# SCH_New-Project2_2024-12-12_1.net
KiCad netlist of a schematic drawn in EasyEDA
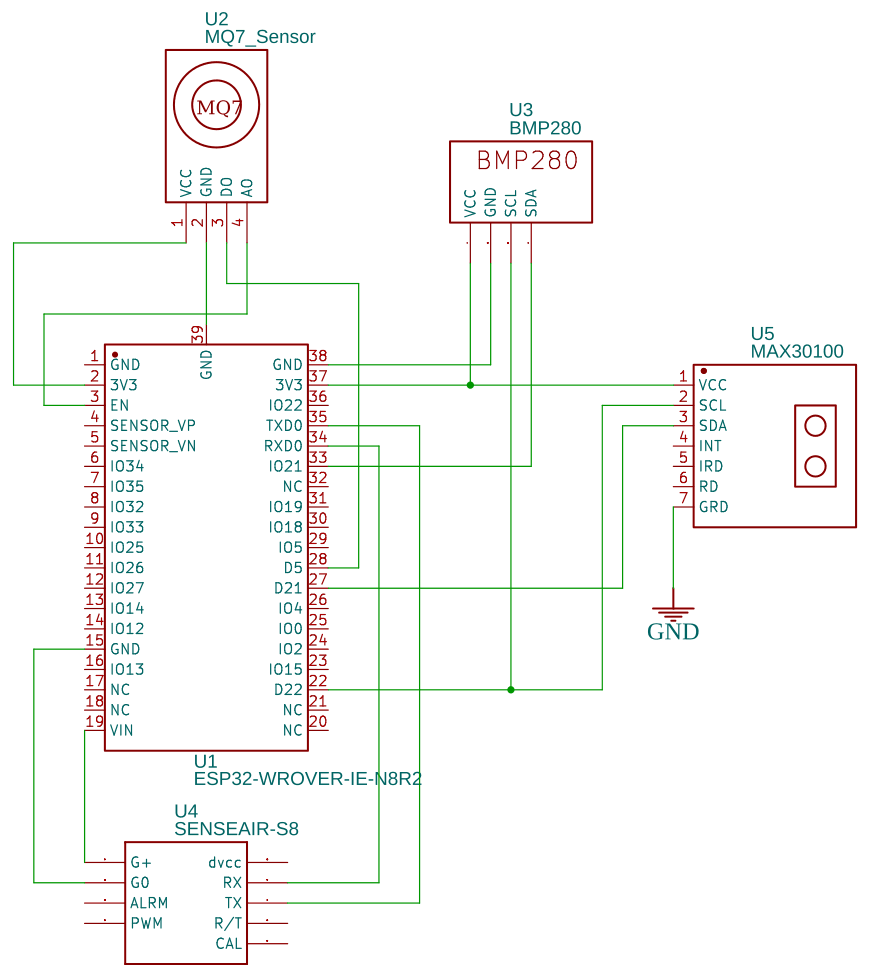
[diagram p0: schematic sheet]

(export (version "E")
  (design (tool "Eeschema 10.0.6"))
  (components
    (comp (ref "U1")
      (value "ESP32-WROVER-IE-N8R2")
      (fields (field (name "Manufacturer") "ESPRESSIF(乐鑫)"))
      (libsource (lib "") (part "ESP32-WROVER-IE-N8R2"))
    )
    (comp (ref "U2") (value "MQ7_Sensor") (libsource (lib "") (part "MQ7_Sensor")))
    (comp (ref "U3") (value "BMP280") (libsource (lib "") (part "BMP280")))
    (comp (ref "U4")
      (value "SENSEAIR-S8")
      (fields (field (name "Manufacturer Part") "SENSEAIR S8"))
      (libsource (lib "") (part "SENSEAIR-S8"))
    )
    (comp (ref "U5")
      (value "MAX30100")
      (fields (field (name "Manufacturer Part") "MAX30100EFD+") (field (name "Manufacturer") "MAXIM"))
      (libsource (lib "") (part "MAX30100"))
    )
  )
  (nets
    (net (code "1") (name "GND") (class "Default")
      (node (ref "U5") (pin "7") (pinfunction "GRD_7") (pintype "unspecified"))
    )
    (net (code "2") (name "Net-(U1-D5)") (class "Default")
      (node (ref "U1") (pin "28") (pinfunction "D5_28") (pintype "unspecified"))
      (node (ref "U2") (pin "3") (pinfunction "DO_3") (pintype "unspecified"))
    )
    (net (code "3") (name "Net-(U1-D21)") (class "Default")
      (node (ref "U1") (pin "27") (pinfunction "D21_27") (pintype "unspecified"))
      (node (ref "U5") (pin "3") (pinfunction "SDA_3") (pintype "unspecified"))
    )
    (net (code "4") (name "Net-(U1-D22)") (class "Default")
      (node (ref "U1") (pin "22") (pinfunction "D22_22") (pintype "unspecified"))
      (node (ref "U3") (pin "5") (pinfunction "SCL_5") (pintype "unspecified"))
      (node (ref "U5") (pin "2") (pinfunction "SCL_2") (pintype "unspecified"))
    )
    (net (code "5") (name "Net-(U1-EN)") (class "Default")
      (node (ref "U1") (pin "3") (pinfunction "EN_3") (pintype "unspecified"))
      (node (ref "U2") (pin "4") (pinfunction "AO_4") (pintype "unspecified"))
    )
    (net (code "6") (name "Net-(U1-GND-Pad15)") (class "Default")
      (node (ref "U1") (pin "15") (pinfunction "GND_15") (pintype "unspecified"))
      (node (ref "U4") (pin "G0") (pinfunction "G0_G0") (pintype "unspecified"))
    )
    (net (code "7") (name "Net-(U1-IO21)") (class "Default")
      (node (ref "U1") (pin "33") (pinfunction "IO21_33") (pintype "unspecified"))
      (node (ref "U3") (pin "4") (pinfunction "SDA_4") (pintype "unspecified"))
    )
    (net (code "8") (name "Net-(U1-RXD0)") (class "Default")
      (node (ref "U1") (pin "34") (pinfunction "RXD0_34") (pintype "unspecified"))
      (node (ref "U4") (pin "RX") (pinfunction "RX_RX") (pintype "unspecified"))
    )
    (net (code "9") (name "Net-(U1-TXD0)") (class "Default")
      (node (ref "U1") (pin "35") (pinfunction "TXD0_35") (pintype "unspecified"))
      (node (ref "U4") (pin "TX") (pinfunction "TX_TX") (pintype "unspecified"))
    )
    (net (code "10") (name "Net-(U1-VIN)") (class "Default")
      (node (ref "U1") (pin "19") (pinfunction "VIN_19") (pintype "unspecified"))
      (node (ref "U4") (pin "G+") (pinfunction "G+_G+") (pintype "unspecified"))
    )
    (net (code "11") (name "Net-(U2-GND)") (class "Default")
      (node (ref "U1") (pin "39") (pinfunction "GND_39") (pintype "unspecified"))
      (node (ref "U2") (pin "2") (pinfunction "GND_2") (pintype "unspecified"))
    )
    (net (code "12") (name "Net-(U2-VCC)") (class "Default")
      (node (ref "U1") (pin "2") (pinfunction "3V3_2") (pintype "unspecified"))
      (node (ref "U2") (pin "1") (pinfunction "VCC_1") (pintype "unspecified"))
    )
    (net (code "13") (name "Net-(U3-GND)") (class "Default")
      (node (ref "U1") (pin "38") (pinfunction "GND_38") (pintype "unspecified"))
      (node (ref "U3") (pin "6") (pinfunction "GND_6") (pintype "unspecified"))
    )
    (net (code "14") (name "Net-(U3-VCC)") (class "Default")
      (node (ref "U1") (pin "37") (pinfunction "3V3_37") (pintype "unspecified"))
      (node (ref "U3") (pin "7") (pinfunction "VCC_7") (pintype "unspecified"))
      (node (ref "U5") (pin "1") (pinfunction "VCC_1") (pintype "unspecified"))
    )
    (net (code "15") (name "unconnected-(U1-GND-Pad1)") (class "Default")
      (node (ref "U1") (pin "1") (pinfunction "GND_1") (pintype "unspecified"))
    )
    (net (code "16") (name "unconnected-(U1-IO0-Pad25)") (class "Default")
      (node (ref "U1") (pin "25") (pinfunction "IO0_25") (pintype "unspecified"))
    )
    (net (code "17") (name "unconnected-(U1-IO2-Pad24)") (class "Default")
      (node (ref "U1") (pin "24") (pinfunction "IO2_24") (pintype "unspecified"))
    )
    (net (code "18") (name "unconnected-(U1-IO4-Pad26)") (class "Default")
      (node (ref "U1") (pin "26") (pinfunction "IO4_26") (pintype "unspecified"))
    )
    (net (code "19") (name "unconnected-(U1-IO5-Pad29)") (class "Default")
      (node (ref "U1") (pin "29") (pinfunction "IO5_29") (pintype "unspecified"))
    )
    (net (code "20") (name "unconnected-(U1-IO12-Pad14)") (class "Default")
      (node (ref "U1") (pin "14") (pinfunction "IO12_14") (pintype "unspecified"))
    )
    (net (code "21") (name "unconnected-(U1-IO13-Pad16)") (class "Default")
      (node (ref "U1") (pin "16") (pinfunction "IO13_16") (pintype "unspecified"))
    )
    (net (code "22") (name "unconnected-(U1-IO14-Pad13)") (class "Default")
      (node (ref "U1") (pin "13") (pinfunction "IO14_13") (pintype "unspecified"))
    )
    (net (code "23") (name "unconnected-(U1-IO15-Pad23)") (class "Default")
      (node (ref "U1") (pin "23") (pinfunction "IO15_23") (pintype "unspecified"))
    )
    (net (code "24") (name "unconnected-(U1-IO18-Pad30)") (class "Default")
      (node (ref "U1") (pin "30") (pinfunction "IO18_30") (pintype "unspecified"))
    )
    (net (code "25") (name "unconnected-(U1-IO19-Pad31)") (class "Default")
      (node (ref "U1") (pin "31") (pinfunction "IO19_31") (pintype "unspecified"))
    )
    (net (code "26") (name "unconnected-(U1-IO22-Pad36)") (class "Default")
      (node (ref "U1") (pin "36") (pinfunction "IO22_36") (pintype "unspecified"))
    )
    (net (code "27") (name "unconnected-(U1-IO25-Pad10)") (class "Default")
      (node (ref "U1") (pin "10") (pinfunction "IO25_10") (pintype "unspecified"))
    )
    (net (code "28") (name "unconnected-(U1-IO26-Pad11)") (class "Default")
      (node (ref "U1") (pin "11") (pinfunction "IO26_11") (pintype "unspecified"))
    )
    (net (code "29") (name "unconnected-(U1-IO27-Pad12)") (class "Default")
      (node (ref "U1") (pin "12") (pinfunction "IO27_12") (pintype "unspecified"))
    )
    (net (code "30") (name "unconnected-(U1-IO32-Pad8)") (class "Default")
      (node (ref "U1") (pin "8") (pinfunction "IO32_8") (pintype "unspecified"))
    )
    (net (code "31") (name "unconnected-(U1-IO33-Pad9)") (class "Default")
      (node (ref "U1") (pin "9") (pinfunction "IO33_9") (pintype "unspecified"))
    )
    (net (code "32") (name "unconnected-(U1-IO34-Pad6)") (class "Default")
      (node (ref "U1") (pin "6") (pinfunction "IO34_6") (pintype "unspecified"))
    )
    (net (code "33") (name "unconnected-(U1-IO35-Pad7)") (class "Default")
      (node (ref "U1") (pin "7") (pinfunction "IO35_7") (pintype "unspecified"))
    )
    (net (code "34") (name "unconnected-(U1-NC-Pad17)") (class "Default")
      (node (ref "U1") (pin "17") (pinfunction "NC_17") (pintype "unspecified"))
    )
    (net (code "35") (name "unconnected-(U1-NC-Pad18)") (class "Default")
      (node (ref "U1") (pin "18") (pinfunction "NC_18") (pintype "unspecified"))
    )
    (net (code "36") (name "unconnected-(U1-NC-Pad20)") (class "Default")
      (node (ref "U1") (pin "20") (pinfunction "NC_20") (pintype "unspecified"))
    )
    (net (code "37") (name "unconnected-(U1-NC-Pad21)") (class "Default")
      (node (ref "U1") (pin "21") (pinfunction "NC_21") (pintype "unspecified"))
    )
    (net (code "38") (name "unconnected-(U1-NC-Pad32)") (class "Default")
      (node (ref "U1") (pin "32") (pinfunction "NC_32") (pintype "unspecified"))
    )
    (net (code "39") (name "unconnected-(U1-SENSOR_VN-Pad5)") (class "Default")
      (node (ref "U1") (pin "5") (pinfunction "SENSOR_VN_5") (pintype "unspecified"))
    )
    (net (code "40") (name "unconnected-(U1-SENSOR_VP-Pad4)") (class "Default")
      (node (ref "U1") (pin "4") (pinfunction "SENSOR_VP_4") (pintype "unspecified"))
    )
    (net (code "41") (name "unconnected-(U4-PadALRM)") (class "Default")
      (node (ref "U4") (pin "ALRM") (pinfunction "ALRM_ALRM") (pintype "unspecified"))
    )
    (net (code "42") (name "unconnected-(U4-PadCAL)") (class "Default")
      (node (ref "U4") (pin "CAL") (pinfunction "CAL_CAL") (pintype "unspecified"))
    )
    (net (code "43") (name "unconnected-(U4-PadPWM)") (class "Default")
      (node (ref "U4") (pin "PWM") (pinfunction "PWM_PWM") (pintype "unspecified"))
    )
    (net (code "44") (name "unconnected-(U4-PadR{slash}T)") (class "Default")
      (node (ref "U4") (pin "R/T") (pinfunction "R/T_R/T") (pintype "unspecified"))
    )
    (net (code "45") (name "unconnected-(U4-dvcc-Pad3.3V)") (class "Default")
      (node (ref "U4") (pin "3.3V") (pinfunction "dvcc_3.3V") (pintype "unspecified"))
    )
    (net (code "46") (name "unconnected-(U5-INT-Pad4)") (class "Default")
      (node (ref "U5") (pin "4") (pinfunction "INT_4") (pintype "unspecified"))
    )
    (net (code "47") (name "unconnected-(U5-IRD-Pad5)") (class "Default")
      (node (ref "U5") (pin "5") (pinfunction "IRD_5") (pintype "unspecified"))
    )
    (net (code "48") (name "unconnected-(U5-RD-Pad6)") (class "Default")
      (node (ref "U5") (pin "6") (pinfunction "RD_6") (pintype "unspecified"))
    )
  )
)
